# sensors_board.net
KiCad netlist of a schematic drawn in EAGLE
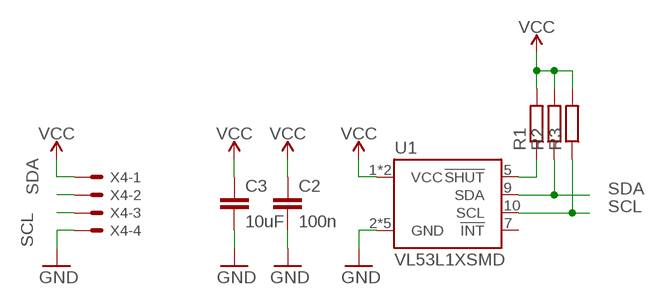
[diagram p0: schematic, sheet 1]

(export (version "E")
  (design (tool "Eeschema 10.0.6"))
  (components
    (comp (ref "C2")
      (value "100n")
      (footprint "eagle-import:C0805")
      (libsource (lib "eagle-import") (part "C-EUC0805"))
    )
    (comp (ref "C3")
      (value "10uF")
      (footprint "eagle-import:C0805")
      (libsource (lib "eagle-import") (part "C-EUC0805"))
    )
    (comp (ref "R1")
      (value "R-EU_M0805")
      (footprint "eagle-import:M0805")
      (libsource (lib "eagle-import") (part "R-EU_M0805"))
    )
    (comp (ref "R2")
      (value "R-EU_M0805")
      (footprint "eagle-import:M0805")
      (libsource (lib "eagle-import") (part "R-EU_M0805"))
    )
    (comp (ref "R3")
      (value "R-EU_M0805")
      (footprint "eagle-import:M0805")
      (libsource (lib "eagle-import") (part "R-EU_M0805"))
    )
    (comp (ref "U1")
      (value "VL53L1XSMD")
      (footprint "eagle-import:VL53L1X")
      (libsource (lib "eagle-import") (part "VL53L1XSMD"))
    )
    (comp (ref "X4")
      (value "52745-0490")
      (footprint "eagle-import:52745-0490")
      (fields (field (name "MF") "MOLEX"))
      (libsource (lib "eagle-import") (part "52745-0490"))
    )
  )
  (nets
    (net (code "1") (name "/SCL") (class "Default")
      (node (ref "R3") (pin "1") (pinfunction "1_1") (pintype "passive"))
      (node (ref "U1") (pin "10") (pinfunction "SCL_10") (pintype "bidirectional"))
      (node (ref "X4") (pin "3") (pinfunction "S_3") (pintype "passive"))
    )
    (net (code "2") (name "/SDA") (class "Default")
      (node (ref "R2") (pin "1") (pinfunction "1_1") (pintype "passive"))
      (node (ref "U1") (pin "9") (pinfunction "SDA_9") (pintype "bidirectional"))
      (node (ref "X4") (pin "2") (pinfunction "S_2") (pintype "passive"))
    )
    (net (code "3") (name "GND") (class "Default")
      (node (ref "C2") (pin "2") (pinfunction "2_2") (pintype "passive"))
      (node (ref "C3") (pin "2") (pinfunction "2_2") (pintype "passive"))
      (node (ref "U1") (pin "12") (pinfunction "GND_12") (pintype "bidirectional"))
      (node (ref "U1") (pin "2") (pinfunction "GND_2") (pintype "bidirectional"))
      (node (ref "U1") (pin "3") (pinfunction "GND_3") (pintype "bidirectional"))
      (node (ref "U1") (pin "4") (pinfunction "GND_4") (pintype "bidirectional"))
      (node (ref "U1") (pin "6") (pinfunction "GND_6") (pintype "bidirectional"))
      (node (ref "X4") (pin "4") (pinfunction "S_4") (pintype "passive"))
    )
    (net (code "4") (name "Net-(U1-~{SHUT})") (class "Default")
      (node (ref "R1") (pin "1") (pinfunction "1_1") (pintype "passive"))
      (node (ref "U1") (pin "5") (pinfunction "~{SHUT}_5") (pintype "bidirectional"))
    )
    (net (code "5") (name "VCC") (class "Default")
      (node (ref "C2") (pin "1") (pinfunction "1_1") (pintype "passive"))
      (node (ref "C3") (pin "1") (pinfunction "1_1") (pintype "passive"))
      (node (ref "R1") (pin "2") (pinfunction "2_2") (pintype "passive"))
      (node (ref "R2") (pin "2") (pinfunction "2_2") (pintype "passive"))
      (node (ref "R3") (pin "2") (pinfunction "2_2") (pintype "passive"))
      (node (ref "U1") (pin "1") (pinfunction "VCC_1") (pintype "bidirectional"))
      (node (ref "U1") (pin "11") (pinfunction "VCC_11") (pintype "bidirectional"))
      (node (ref "X4") (pin "1") (pinfunction "S_1") (pintype "passive"))
    )
    (net (code "6") (name "unconnected-(U1-~{INT}-Pad7)") (class "Default")
      (node (ref "U1") (pin "7") (pinfunction "~{INT}_7") (pintype "bidirectional"))
    )
  )
)
